# CoffeeRoaster_FrontPanelBoard_2023_02_25.net
KiCad netlist of a schematic drawn in EAGLE
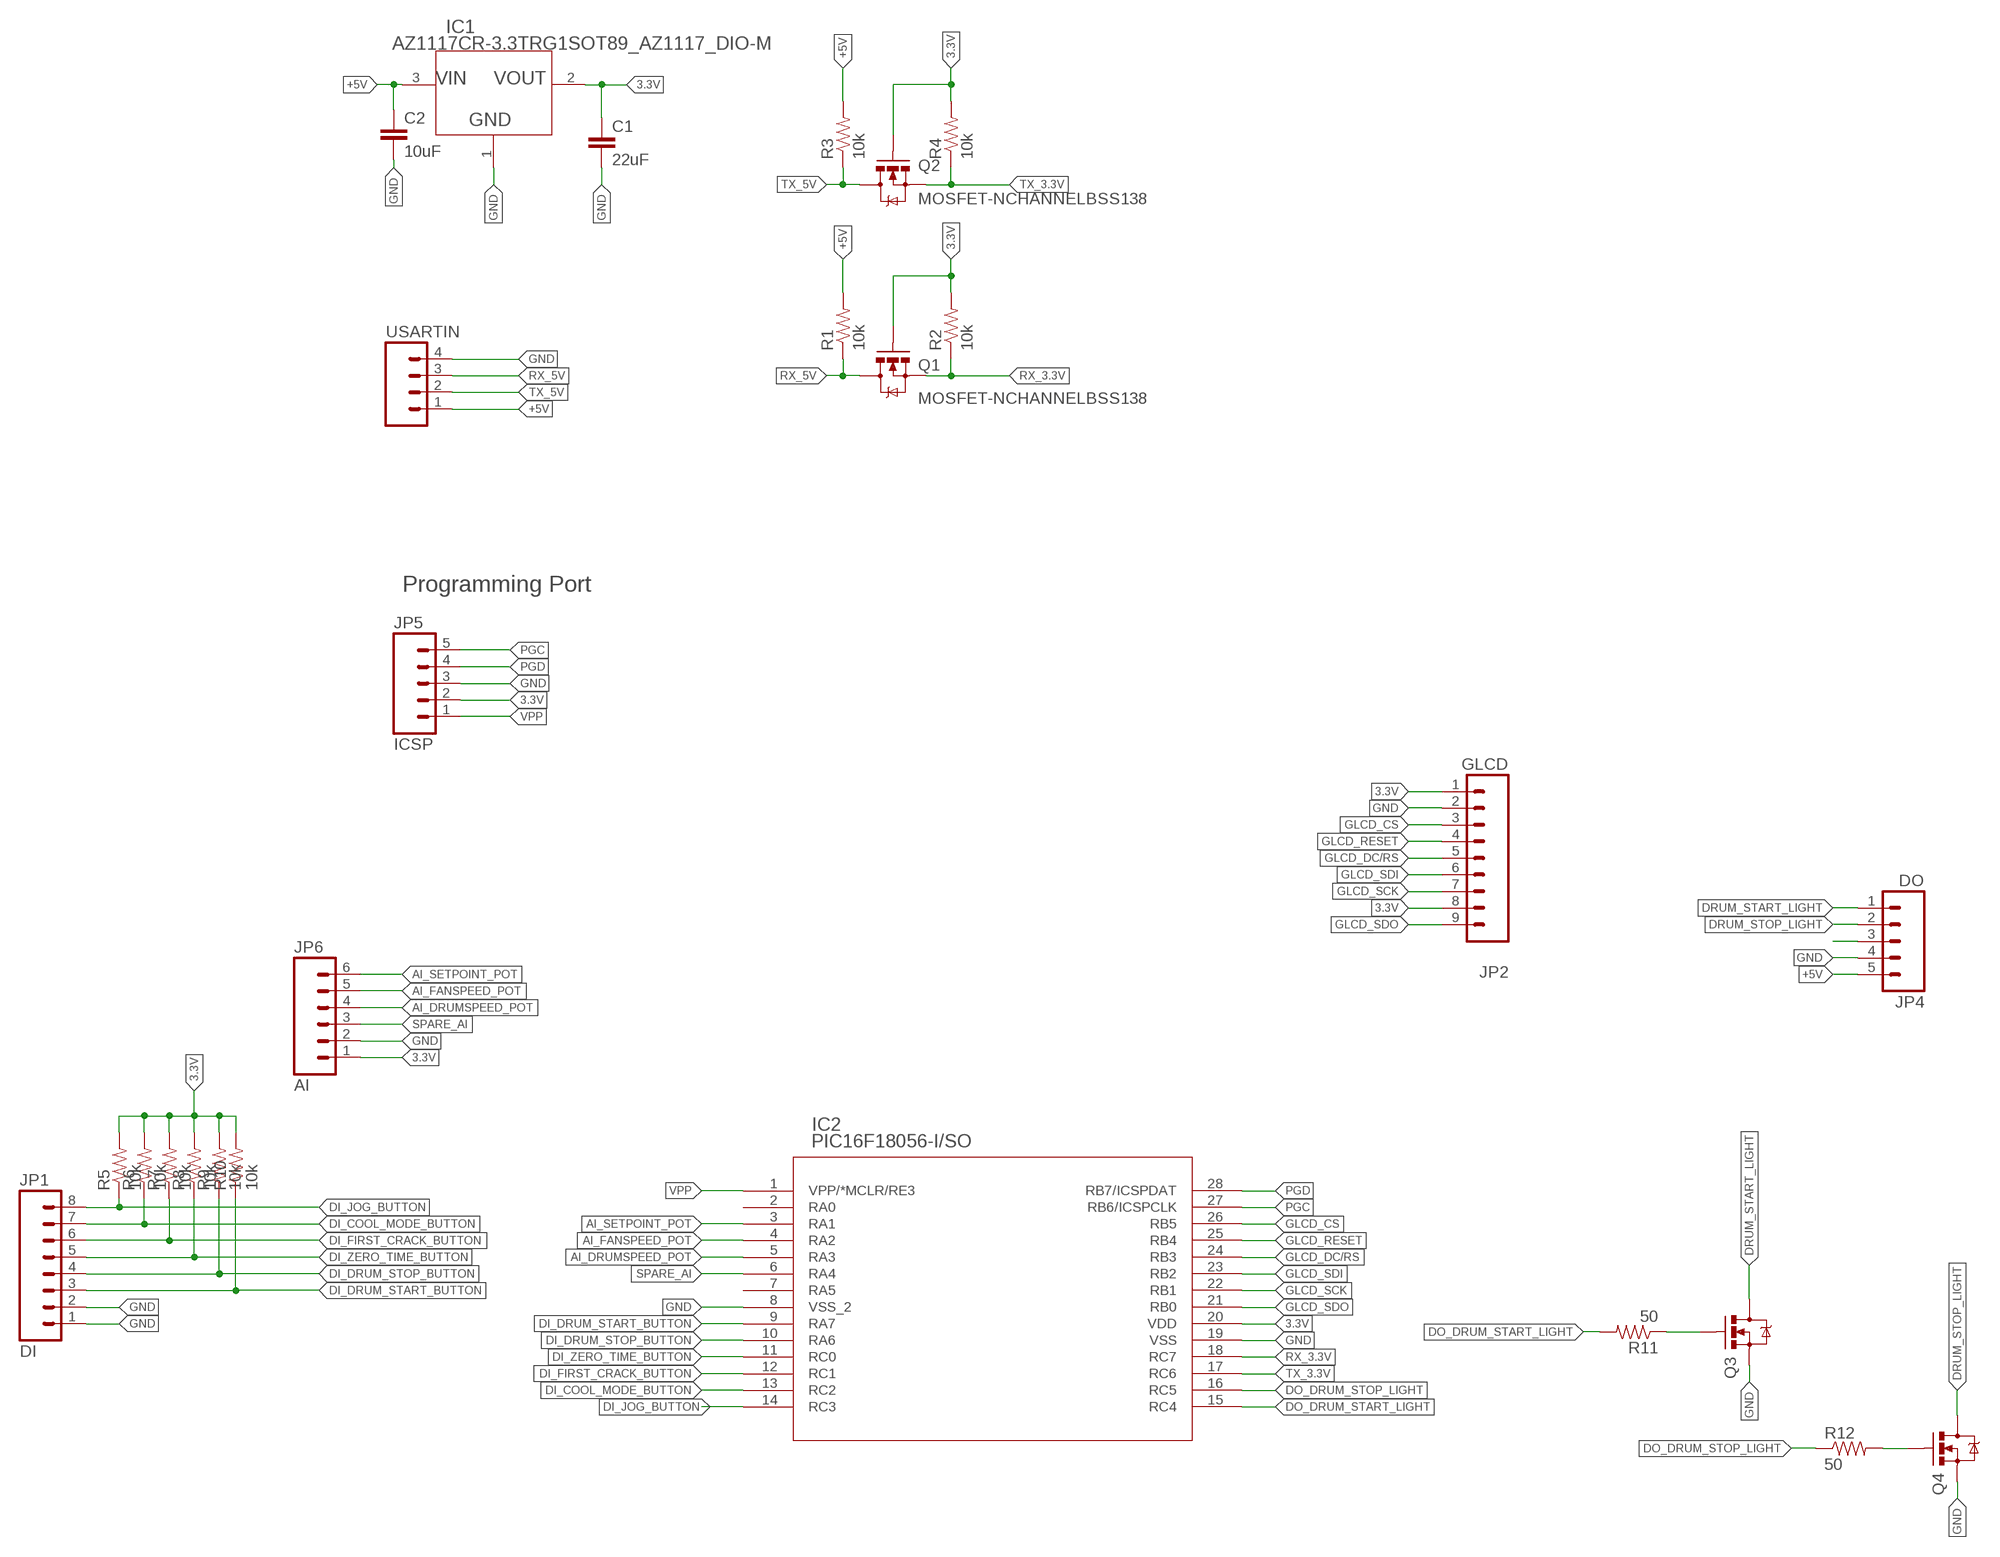
[diagram p0: schematic, sheet 1]

(export (version "E")
  (design (tool "Eeschema 10.0.6"))
  (components
    (comp (ref "C1")
      (value "22uF")
      (footprint "eagle-import:1206")
      (libsource (lib "eagle-import") (part "CAP1206"))
    )
    (comp (ref "C2")
      (value "10uF")
      (footprint "eagle-import:1206")
      (libsource (lib "eagle-import") (part "CAP1206"))
    )
    (comp (ref "IC1")
      (value "AZ1117CR-3.3TRG1SOT89_AZ1117_DIO-M")
      (footprint "eagle-import:SOT89_AZ1117_DIO-M")
      (fields
        (field (name "MANUFACTURER_PART_NUMBER") "AZ1117CR-3.3TRG1")
        (field (name "COPYRIGHT") "Copyright (C) 2022 Ultra Librarian. All rights reserved.")
      )
      (libsource (lib "eagle-import") (part "AZ1117CR-3.3TRG1SOT89_AZ1117_DIO-M"))
    )
    (comp (ref "IC2")
      (value "PIC16F18056-I/SO")
      (footprint "eagle-import:SOIC28-W_MC")
      (fields
        (field (name "MANUFACTURER_PART_NUMBER") "pic16f1773-x/so")
        (field (name "COPYRIGHT") "Copyright (C) 2016 Accelerated Designs. All rights reserved")
      )
      (libsource (lib "eagle-import") (part "PIC16F1773-X/SO"))
    )
    (comp (ref "JP1")
      (value "DI")
      (footprint "eagle-import:1X08_LOCK_LONGPADS")
      (libsource (lib "eagle-import") (part "M08LOCK_LONGPADS"))
    )
    (comp (ref "JP2")
      (value "GLCD")
      (footprint "eagle-import:1X09_LOCK_LONGPADS")
      (libsource (lib "eagle-import") (part "M09LOCK-LONGPADS"))
    )
    (comp (ref "JP4")
      (value "DO")
      (footprint "eagle-import:1X05_LOCK_LONGPADS")
      (libsource (lib "eagle-import") (part "M05LOCK_LONGPADS"))
    )
    (comp (ref "JP5")
      (value "ICSP")
      (footprint "eagle-import:1X05")
      (libsource (lib "eagle-import") (part "M05PTH"))
    )
    (comp (ref "JP6")
      (value "AI")
      (footprint "eagle-import:1X06_LOCK_LONGPADS")
      (libsource (lib "eagle-import") (part "M06LOCK_LONGPADS"))
    )
    (comp (ref "Q1")
      (value "MOSFET-NCHANNELBSS138")
      (footprint "eagle-import:SOT23-3")
      (libsource (lib "eagle-import") (part "MOSFET-NCHANNELBSS138"))
    )
    (comp (ref "Q2")
      (value "MOSFET-NCHANNELBSS138")
      (footprint "eagle-import:SOT23-3")
      (libsource (lib "eagle-import") (part "MOSFET-NCHANNELBSS138"))
    )
    (comp (ref "Q3")
      (value "MOSFET-NCHANNELBSS138")
      (footprint "eagle-import:SOT23-3")
      (libsource (lib "eagle-import") (part "MOSFET-NCHANNELBSS138"))
    )
    (comp (ref "Q4")
      (value "MOSFET-NCHANNELBSS138")
      (footprint "eagle-import:SOT23-3")
      (libsource (lib "eagle-import") (part "MOSFET-NCHANNELBSS138"))
    )
    (comp (ref "R1")
      (value "10k")
      (footprint "eagle-import:1206")
      (libsource (lib "eagle-import") (part "RESISTOR1206"))
    )
    (comp (ref "R2")
      (value "10k")
      (footprint "eagle-import:1206")
      (libsource (lib "eagle-import") (part "RESISTOR1206"))
    )
    (comp (ref "R3")
      (value "10k")
      (footprint "eagle-import:1206")
      (libsource (lib "eagle-import") (part "RESISTOR1206"))
    )
    (comp (ref "R4")
      (value "10k")
      (footprint "eagle-import:1206")
      (libsource (lib "eagle-import") (part "RESISTOR1206"))
    )
    (comp (ref "R5")
      (value "10k")
      (footprint "eagle-import:1206")
      (libsource (lib "eagle-import") (part "RESISTOR1206"))
    )
    (comp (ref "R6")
      (value "10k")
      (footprint "eagle-import:1206")
      (libsource (lib "eagle-import") (part "RESISTOR1206"))
    )
    (comp (ref "R7")
      (value "10k")
      (footprint "eagle-import:1206")
      (libsource (lib "eagle-import") (part "RESISTOR1206"))
    )
    (comp (ref "R8")
      (value "10k")
      (footprint "eagle-import:1206")
      (libsource (lib "eagle-import") (part "RESISTOR1206"))
    )
    (comp (ref "R9")
      (value "10k")
      (footprint "eagle-import:1206")
      (libsource (lib "eagle-import") (part "RESISTOR1206"))
    )
    (comp (ref "R10")
      (value "10k")
      (footprint "eagle-import:1206")
      (libsource (lib "eagle-import") (part "RESISTOR1206"))
    )
    (comp (ref "R11")
      (value "50")
      (footprint "eagle-import:1206")
      (libsource (lib "eagle-import") (part "RESISTOR1206"))
    )
    (comp (ref "R12")
      (value "50")
      (footprint "eagle-import:1206")
      (libsource (lib "eagle-import") (part "RESISTOR1206"))
    )
    (comp (ref "USARTIN")
      (value "M04LONGPADS")
      (footprint "eagle-import:1X04_LONGPADS")
      (libsource (lib "eagle-import") (part "M04LONGPADS"))
    )
  )
  (nets
    (net (code "1") (name "+5V") (class "Default")
      (node (ref "C2") (pin "1") (pinfunction "1_1") (pintype "passive"))
      (node (ref "IC1") (pin "3") (pinfunction "INPUT_3") (pintype "input"))
      (node (ref "JP4") (pin "5") (pinfunction "5_5") (pintype "passive"))
      (node (ref "R1") (pin "2") (pinfunction "2_2") (pintype "passive"))
      (node (ref "R3") (pin "2") (pinfunction "2_2") (pintype "passive"))
      (node (ref "USARTIN") (pin "1") (pinfunction "1_1") (pintype "passive"))
    )
    (net (code "2") (name "3.3V") (class "Default")
      (node (ref "C1") (pin "1") (pinfunction "1_1") (pintype "passive"))
      (node (ref "IC1") (pin "2") (pinfunction "OUTPUT_2") (pintype "output"))
      (node (ref "IC2") (pin "20") (pinfunction "VDD_20") (pintype "power_in"))
      (node (ref "JP2") (pin "1") (pinfunction "1_1") (pintype "passive"))
      (node (ref "JP2") (pin "8") (pinfunction "8_8") (pintype "passive"))
      (node (ref "JP5") (pin "2") (pinfunction "2_2") (pintype "passive"))
      (node (ref "JP6") (pin "1") (pinfunction "1_1") (pintype "passive"))
      (node (ref "Q1") (pin "1") (pinfunction "G_1") (pintype "passive"))
      (node (ref "Q2") (pin "1") (pinfunction "G_1") (pintype "passive"))
      (node (ref "R10") (pin "2") (pinfunction "2_2") (pintype "passive"))
      (node (ref "R2") (pin "2") (pinfunction "2_2") (pintype "passive"))
      (node (ref "R4") (pin "2") (pinfunction "2_2") (pintype "passive"))
      (node (ref "R5") (pin "2") (pinfunction "2_2") (pintype "passive"))
      (node (ref "R6") (pin "2") (pinfunction "2_2") (pintype "passive"))
      (node (ref "R7") (pin "2") (pinfunction "2_2") (pintype "passive"))
      (node (ref "R8") (pin "2") (pinfunction "2_2") (pintype "passive"))
      (node (ref "R9") (pin "2") (pinfunction "2_2") (pintype "passive"))
    )
    (net (code "3") (name "AI_DRUMSPEED_POT") (class "Default")
      (node (ref "IC2") (pin "5") (pinfunction "RA3_5") (pintype "bidirectional"))
      (node (ref "JP6") (pin "4") (pinfunction "4_4") (pintype "passive"))
    )
    (net (code "4") (name "AI_FANSPEED_POT") (class "Default")
      (node (ref "IC2") (pin "4") (pinfunction "RA2_4") (pintype "bidirectional"))
      (node (ref "JP6") (pin "5") (pinfunction "5_5") (pintype "passive"))
    )
    (net (code "5") (name "AI_SETPOINT_POT") (class "Default")
      (node (ref "IC2") (pin "3") (pinfunction "RA1_3") (pintype "bidirectional"))
      (node (ref "JP6") (pin "6") (pinfunction "6_6") (pintype "passive"))
    )
    (net (code "6") (name "DI_COOL_MODE_BUTTON") (class "Default")
      (node (ref "IC2") (pin "13") (pinfunction "RC2_13") (pintype "bidirectional"))
      (node (ref "JP1") (pin "7") (pinfunction "7_7") (pintype "passive"))
      (node (ref "R6") (pin "1") (pinfunction "1_1") (pintype "passive"))
    )
    (net (code "7") (name "DI_DRUM_START_BUTTON") (class "Default")
      (node (ref "IC2") (pin "9") (pinfunction "RA7_9") (pintype "bidirectional"))
      (node (ref "JP1") (pin "3") (pinfunction "3_3") (pintype "passive"))
      (node (ref "R10") (pin "1") (pinfunction "1_1") (pintype "passive"))
    )
    (net (code "8") (name "DI_DRUM_STOP_BUTTON") (class "Default")
      (node (ref "IC2") (pin "10") (pinfunction "RA6_10") (pintype "bidirectional"))
      (node (ref "JP1") (pin "4") (pinfunction "4_4") (pintype "passive"))
      (node (ref "R9") (pin "1") (pinfunction "1_1") (pintype "passive"))
    )
    (net (code "9") (name "DI_FIRST_CRACK_BUTTON") (class "Default")
      (node (ref "IC2") (pin "12") (pinfunction "RC1_12") (pintype "bidirectional"))
      (node (ref "JP1") (pin "6") (pinfunction "6_6") (pintype "passive"))
      (node (ref "R7") (pin "1") (pinfunction "1_1") (pintype "passive"))
    )
    (net (code "10") (name "DI_JOG_BUTTON") (class "Default")
      (node (ref "IC2") (pin "14") (pinfunction "RC3_14") (pintype "bidirectional"))
      (node (ref "JP1") (pin "8") (pinfunction "8_8") (pintype "passive"))
      (node (ref "R5") (pin "1") (pinfunction "1_1") (pintype "passive"))
    )
    (net (code "11") (name "DI_ZERO_TIME_BUTTON") (class "Default")
      (node (ref "IC2") (pin "11") (pinfunction "RC0_11") (pintype "bidirectional"))
      (node (ref "JP1") (pin "5") (pinfunction "5_5") (pintype "passive"))
      (node (ref "R8") (pin "1") (pinfunction "1_1") (pintype "passive"))
    )
    (net (code "12") (name "DO_DRUM_START_LIGHT") (class "Default")
      (node (ref "IC2") (pin "15") (pinfunction "RC4_15") (pintype "bidirectional"))
      (node (ref "R11") (pin "2") (pinfunction "2_2") (pintype "passive"))
    )
    (net (code "13") (name "DO_DRUM_STOP_LIGHT") (class "Default")
      (node (ref "IC2") (pin "16") (pinfunction "RC5_16") (pintype "bidirectional"))
      (node (ref "R12") (pin "1") (pinfunction "1_1") (pintype "passive"))
    )
    (net (code "14") (name "DRUM_START_LIGHT") (class "Default")
      (node (ref "JP4") (pin "1") (pinfunction "1_1") (pintype "passive"))
      (node (ref "Q3") (pin "3") (pinfunction "D_3") (pintype "passive"))
    )
    (net (code "15") (name "DRUM_STOP_LIGHT") (class "Default")
      (node (ref "JP4") (pin "2") (pinfunction "2_2") (pintype "passive"))
      (node (ref "Q4") (pin "3") (pinfunction "D_3") (pintype "passive"))
    )
    (net (code "16") (name "GLCD_CS") (class "Default")
      (node (ref "IC2") (pin "26") (pinfunction "RB5_26") (pintype "bidirectional"))
      (node (ref "JP2") (pin "3") (pinfunction "3_3") (pintype "passive"))
    )
    (net (code "17") (name "GLCD_DC{slash}RS") (class "Default")
      (node (ref "IC2") (pin "24") (pinfunction "RB3_24") (pintype "bidirectional"))
      (node (ref "JP2") (pin "5") (pinfunction "5_5") (pintype "passive"))
    )
    (net (code "18") (name "GLCD_RESET") (class "Default")
      (node (ref "IC2") (pin "25") (pinfunction "RB4_25") (pintype "bidirectional"))
      (node (ref "JP2") (pin "4") (pinfunction "4_4") (pintype "passive"))
    )
    (net (code "19") (name "GLCD_SCK") (class "Default")
      (node (ref "IC2") (pin "22") (pinfunction "RB1_22") (pintype "bidirectional"))
      (node (ref "JP2") (pin "7") (pinfunction "7_7") (pintype "passive"))
    )
    (net (code "20") (name "GLCD_SDI") (class "Default")
      (node (ref "IC2") (pin "23") (pinfunction "RB2_23") (pintype "bidirectional"))
      (node (ref "JP2") (pin "6") (pinfunction "6_6") (pintype "passive"))
    )
    (net (code "21") (name "GLCD_SDO") (class "Default")
      (node (ref "IC2") (pin "21") (pinfunction "RB0_21") (pintype "bidirectional"))
      (node (ref "JP2") (pin "9") (pinfunction "9_9") (pintype "passive"))
    )
    (net (code "22") (name "GND") (class "Default")
      (node (ref "C1") (pin "2") (pinfunction "2_2") (pintype "passive"))
      (node (ref "C2") (pin "2") (pinfunction "2_2") (pintype "passive"))
      (node (ref "IC1") (pin "1") (pinfunction "ADJ/GND_1") (pintype "passive"))
      (node (ref "IC2") (pin "19") (pinfunction "VSS_19") (pintype "power_in"))
      (node (ref "IC2") (pin "8") (pinfunction "VSS_2_8") (pintype "power_in"))
      (node (ref "JP1") (pin "1") (pinfunction "1_1") (pintype "passive"))
      (node (ref "JP1") (pin "2") (pinfunction "2_2") (pintype "passive"))
      (node (ref "JP2") (pin "2") (pinfunction "2_2") (pintype "passive"))
      (node (ref "JP4") (pin "4") (pinfunction "4_4") (pintype "passive"))
      (node (ref "JP5") (pin "3") (pinfunction "3_3") (pintype "passive"))
      (node (ref "JP6") (pin "2") (pinfunction "2_2") (pintype "passive"))
      (node (ref "Q3") (pin "2") (pinfunction "S_2") (pintype "passive"))
      (node (ref "Q4") (pin "2") (pinfunction "S_2") (pintype "passive"))
      (node (ref "USARTIN") (pin "4") (pinfunction "4_4") (pintype "passive"))
    )
    (net (code "23") (name "Net-(Q3-G)") (class "Default")
      (node (ref "Q3") (pin "1") (pinfunction "G_1") (pintype "passive"))
      (node (ref "R11") (pin "1") (pinfunction "1_1") (pintype "passive"))
    )
    (net (code "24") (name "Net-(Q4-G)") (class "Default")
      (node (ref "Q4") (pin "1") (pinfunction "G_1") (pintype "passive"))
      (node (ref "R12") (pin "2") (pinfunction "2_2") (pintype "passive"))
    )
    (net (code "25") (name "PGC") (class "Default")
      (node (ref "IC2") (pin "27") (pinfunction "RB6/ICSPCLK_27") (pintype "bidirectional"))
      (node (ref "JP5") (pin "5") (pinfunction "5_5") (pintype "passive"))
    )
    (net (code "26") (name "PGD") (class "Default")
      (node (ref "IC2") (pin "28") (pinfunction "RB7/ICSPDAT_28") (pintype "bidirectional"))
      (node (ref "JP5") (pin "4") (pinfunction "4_4") (pintype "passive"))
    )
    (net (code "27") (name "RX_3.3V") (class "Default")
      (node (ref "IC2") (pin "18") (pinfunction "RC7_18") (pintype "bidirectional"))
      (node (ref "Q1") (pin "2") (pinfunction "S_2") (pintype "passive"))
      (node (ref "R2") (pin "1") (pinfunction "1_1") (pintype "passive"))
    )
    (net (code "28") (name "RX_5V") (class "Default")
      (node (ref "Q1") (pin "3") (pinfunction "D_3") (pintype "passive"))
      (node (ref "R1") (pin "1") (pinfunction "1_1") (pintype "passive"))
      (node (ref "USARTIN") (pin "3") (pinfunction "3_3") (pintype "passive"))
    )
    (net (code "29") (name "SPARE_AI") (class "Default")
      (node (ref "IC2") (pin "6") (pinfunction "RA4_6") (pintype "bidirectional"))
      (node (ref "JP6") (pin "3") (pinfunction "3_3") (pintype "passive"))
    )
    (net (code "30") (name "TX_3.3V") (class "Default")
      (node (ref "IC2") (pin "17") (pinfunction "RC6_17") (pintype "bidirectional"))
      (node (ref "Q2") (pin "2") (pinfunction "S_2") (pintype "passive"))
      (node (ref "R4") (pin "1") (pinfunction "1_1") (pintype "passive"))
    )
    (net (code "31") (name "TX_5V") (class "Default")
      (node (ref "Q2") (pin "3") (pinfunction "D_3") (pintype "passive"))
      (node (ref "R3") (pin "1") (pinfunction "1_1") (pintype "passive"))
      (node (ref "USARTIN") (pin "2") (pinfunction "2_2") (pintype "passive"))
    )
    (net (code "32") (name "VPP") (class "Default")
      (node (ref "IC2") (pin "1") (pinfunction "VPP/*MCLR/RE3_1") (pintype "bidirectional"))
      (node (ref "JP5") (pin "1") (pinfunction "1_1") (pintype "passive"))
    )
    (net (code "33") (name "unconnected-(IC2-RA0-Pad2)") (class "Default")
      (node (ref "IC2") (pin "2") (pinfunction "RA0_2") (pintype "bidirectional"))
    )
    (net (code "34") (name "unconnected-(IC2-RA5-Pad7)") (class "Default")
      (node (ref "IC2") (pin "7") (pinfunction "RA5_7") (pintype "bidirectional"))
    )
    (net (code "35") (name "unconnected-(JP4-Pad3)") (class "Default")
      (node (ref "JP4") (pin "3") (pinfunction "3_3") (pintype "passive"))
    )
  )
)
